# EIB_2xA79026-001_small_pins_v1_2_0_30mm.net
KiCad netlist of a schematic drawn in EAGLE
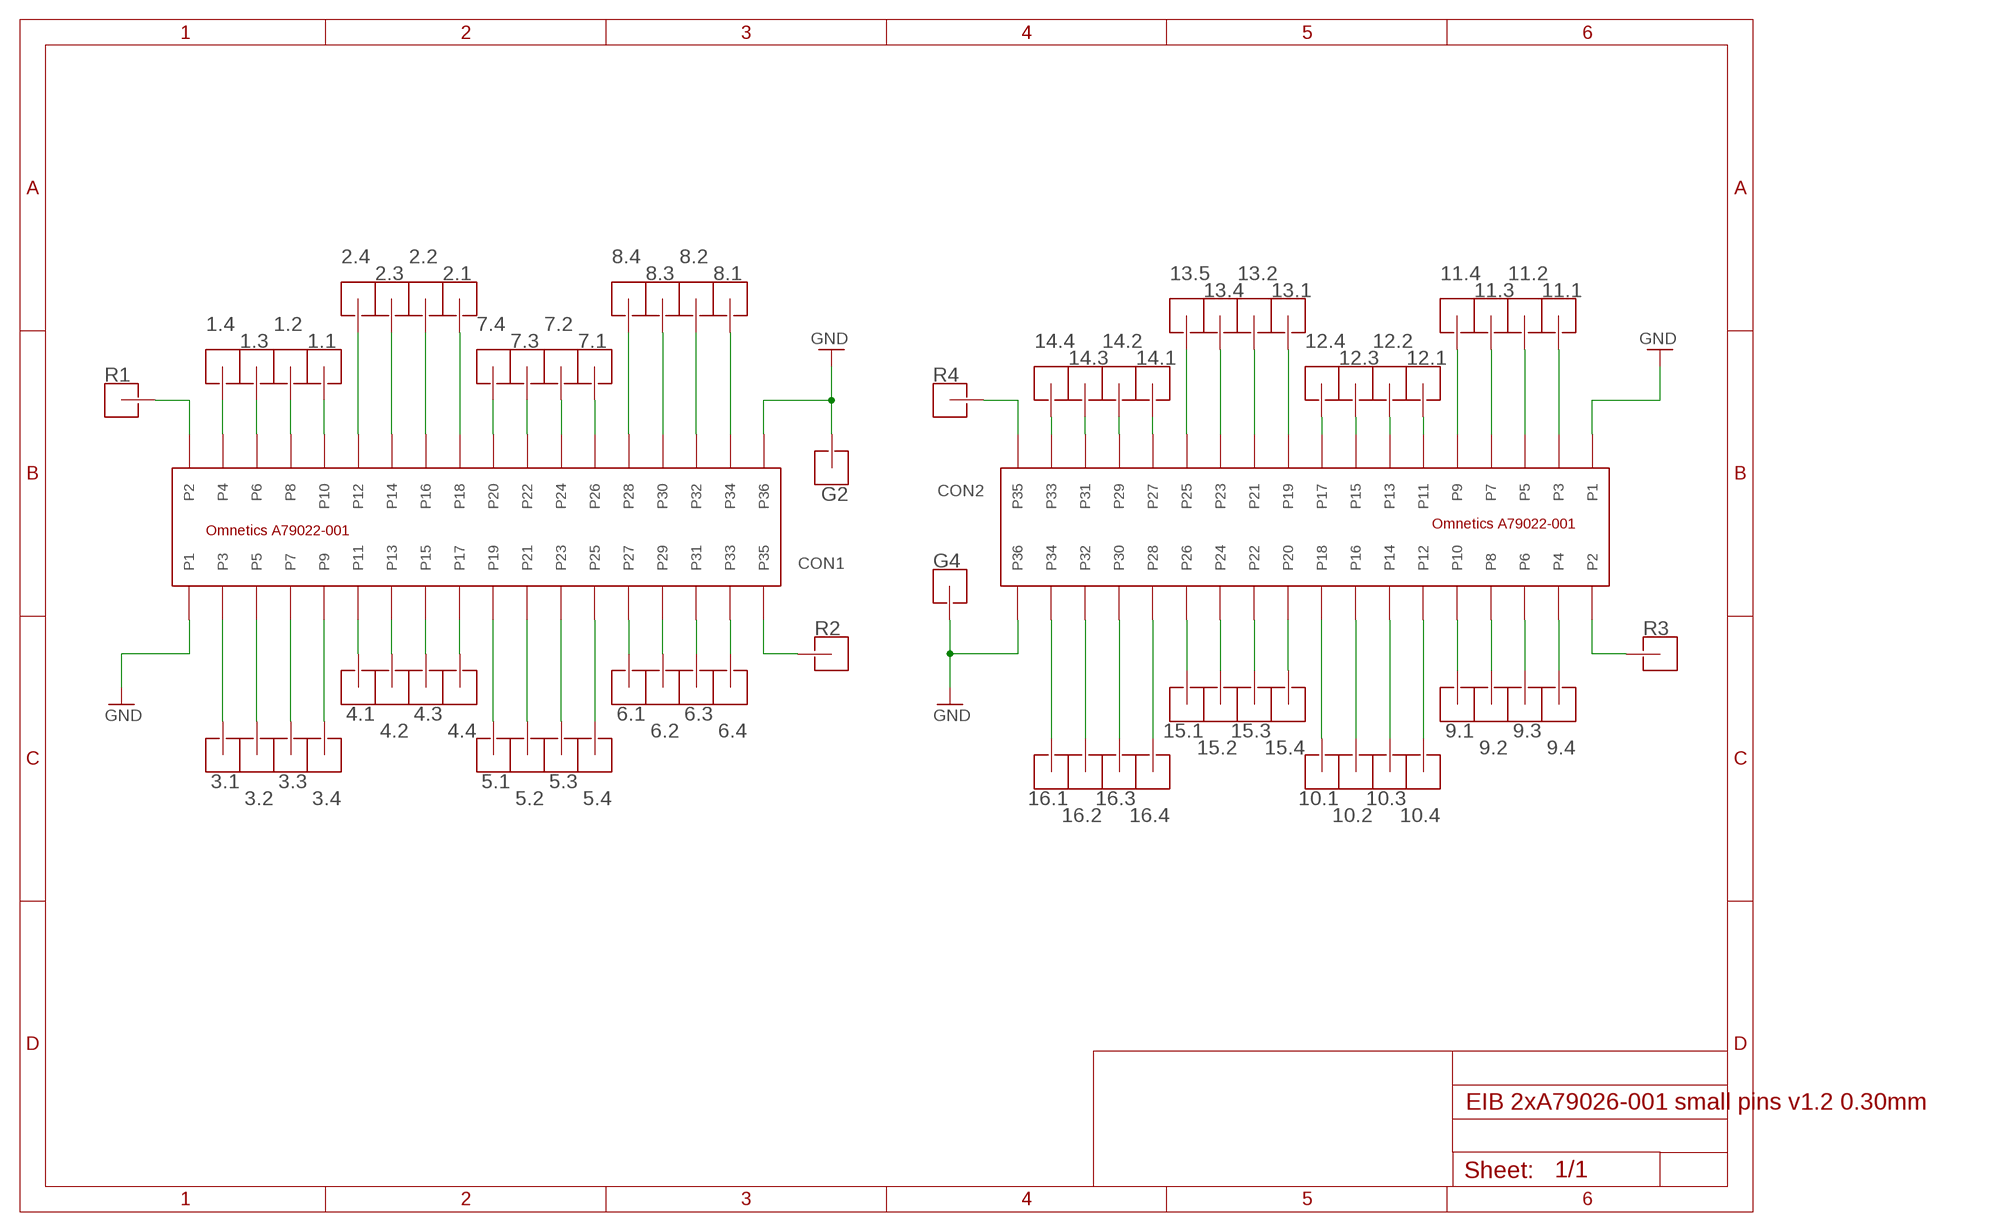
[diagram p0: schematic, sheet 1]

(export (version "E")
  (design (tool "Eeschema 10.0.6"))
  (components
    (comp (ref "1.1")
      (value "HOLE_S_G_PIN_V3")
      (footprint "eagle-import:SMALL_GOLD_PIN_V3")
      (libsource (lib "eagle-import") (part "HOLE_S_G_PIN_V3"))
    )
    (comp (ref "1.2")
      (value "HOLE_S_G_PIN_V3")
      (footprint "eagle-import:SMALL_GOLD_PIN_V3")
      (libsource (lib "eagle-import") (part "HOLE_S_G_PIN_V3"))
    )
    (comp (ref "1.3")
      (value "HOLE_S_G_PIN_V3")
      (footprint "eagle-import:SMALL_GOLD_PIN_V3")
      (libsource (lib "eagle-import") (part "HOLE_S_G_PIN_V3"))
    )
    (comp (ref "1.4")
      (value "HOLE_S_G_PIN_V3")
      (footprint "eagle-import:SMALL_GOLD_PIN_V3")
      (libsource (lib "eagle-import") (part "HOLE_S_G_PIN_V3"))
    )
    (comp (ref "2.1")
      (value "HOLE_S_G_PIN_V3")
      (footprint "eagle-import:SMALL_GOLD_PIN_V3")
      (libsource (lib "eagle-import") (part "HOLE_S_G_PIN_V3"))
    )
    (comp (ref "2.2")
      (value "HOLE_S_G_PIN_V3")
      (footprint "eagle-import:SMALL_GOLD_PIN_V3")
      (libsource (lib "eagle-import") (part "HOLE_S_G_PIN_V3"))
    )
    (comp (ref "2.3")
      (value "HOLE_S_G_PIN_V3")
      (footprint "eagle-import:SMALL_GOLD_PIN_V3")
      (libsource (lib "eagle-import") (part "HOLE_S_G_PIN_V3"))
    )
    (comp (ref "2.4")
      (value "HOLE_S_G_PIN_V3")
      (footprint "eagle-import:SMALL_GOLD_PIN_V3")
      (libsource (lib "eagle-import") (part "HOLE_S_G_PIN_V3"))
    )
    (comp (ref "3.1")
      (value "HOLE_S_G_PIN_V3")
      (footprint "eagle-import:SMALL_GOLD_PIN_V3")
      (libsource (lib "eagle-import") (part "HOLE_S_G_PIN_V3"))
    )
    (comp (ref "3.2")
      (value "HOLE_S_G_PIN_V3")
      (footprint "eagle-import:SMALL_GOLD_PIN_V3")
      (libsource (lib "eagle-import") (part "HOLE_S_G_PIN_V3"))
    )
    (comp (ref "3.3")
      (value "HOLE_S_G_PIN_V3")
      (footprint "eagle-import:SMALL_GOLD_PIN_V3")
      (libsource (lib "eagle-import") (part "HOLE_S_G_PIN_V3"))
    )
    (comp (ref "3.4")
      (value "HOLE_S_G_PIN_V3")
      (footprint "eagle-import:SMALL_GOLD_PIN_V3")
      (libsource (lib "eagle-import") (part "HOLE_S_G_PIN_V3"))
    )
    (comp (ref "4.1")
      (value "HOLE_S_G_PIN_V3")
      (footprint "eagle-import:SMALL_GOLD_PIN_V3")
      (libsource (lib "eagle-import") (part "HOLE_S_G_PIN_V3"))
    )
    (comp (ref "4.2")
      (value "HOLE_S_G_PIN_V3")
      (footprint "eagle-import:SMALL_GOLD_PIN_V3")
      (libsource (lib "eagle-import") (part "HOLE_S_G_PIN_V3"))
    )
    (comp (ref "4.3")
      (value "HOLE_S_G_PIN_V3")
      (footprint "eagle-import:SMALL_GOLD_PIN_V3")
      (libsource (lib "eagle-import") (part "HOLE_S_G_PIN_V3"))
    )
    (comp (ref "4.4")
      (value "HOLE_S_G_PIN_V3")
      (footprint "eagle-import:SMALL_GOLD_PIN_V3")
      (libsource (lib "eagle-import") (part "HOLE_S_G_PIN_V3"))
    )
    (comp (ref "5.1")
      (value "HOLE_S_G_PIN_V3")
      (footprint "eagle-import:SMALL_GOLD_PIN_V3")
      (libsource (lib "eagle-import") (part "HOLE_S_G_PIN_V3"))
    )
    (comp (ref "5.2")
      (value "HOLE_S_G_PIN_V3")
      (footprint "eagle-import:SMALL_GOLD_PIN_V3")
      (libsource (lib "eagle-import") (part "HOLE_S_G_PIN_V3"))
    )
    (comp (ref "5.3")
      (value "HOLE_S_G_PIN_V3")
      (footprint "eagle-import:SMALL_GOLD_PIN_V3")
      (libsource (lib "eagle-import") (part "HOLE_S_G_PIN_V3"))
    )
    (comp (ref "5.4")
      (value "HOLE_S_G_PIN_V3")
      (footprint "eagle-import:SMALL_GOLD_PIN_V3")
      (libsource (lib "eagle-import") (part "HOLE_S_G_PIN_V3"))
    )
    (comp (ref "6.1")
      (value "HOLE_S_G_PIN_V3")
      (footprint "eagle-import:SMALL_GOLD_PIN_V3")
      (libsource (lib "eagle-import") (part "HOLE_S_G_PIN_V3"))
    )
    (comp (ref "6.2")
      (value "HOLE_S_G_PIN_V3")
      (footprint "eagle-import:SMALL_GOLD_PIN_V3")
      (libsource (lib "eagle-import") (part "HOLE_S_G_PIN_V3"))
    )
    (comp (ref "6.3")
      (value "HOLE_S_G_PIN_V3")
      (footprint "eagle-import:SMALL_GOLD_PIN_V3")
      (libsource (lib "eagle-import") (part "HOLE_S_G_PIN_V3"))
    )
    (comp (ref "6.4")
      (value "HOLE_S_G_PIN_V3")
      (footprint "eagle-import:SMALL_GOLD_PIN_V3")
      (libsource (lib "eagle-import") (part "HOLE_S_G_PIN_V3"))
    )
    (comp (ref "7.1")
      (value "HOLE_S_G_PIN_V3")
      (footprint "eagle-import:SMALL_GOLD_PIN_V3")
      (libsource (lib "eagle-import") (part "HOLE_S_G_PIN_V3"))
    )
    (comp (ref "7.2")
      (value "HOLE_S_G_PIN_V3")
      (footprint "eagle-import:SMALL_GOLD_PIN_V3")
      (libsource (lib "eagle-import") (part "HOLE_S_G_PIN_V3"))
    )
    (comp (ref "7.3")
      (value "HOLE_S_G_PIN_V3")
      (footprint "eagle-import:SMALL_GOLD_PIN_V3")
      (libsource (lib "eagle-import") (part "HOLE_S_G_PIN_V3"))
    )
    (comp (ref "7.4")
      (value "HOLE_S_G_PIN_V3")
      (footprint "eagle-import:SMALL_GOLD_PIN_V3")
      (libsource (lib "eagle-import") (part "HOLE_S_G_PIN_V3"))
    )
    (comp (ref "8.1")
      (value "HOLE_S_G_PIN_V3")
      (footprint "eagle-import:SMALL_GOLD_PIN_V3")
      (libsource (lib "eagle-import") (part "HOLE_S_G_PIN_V3"))
    )
    (comp (ref "8.2")
      (value "HOLE_S_G_PIN_V3")
      (footprint "eagle-import:SMALL_GOLD_PIN_V3")
      (libsource (lib "eagle-import") (part "HOLE_S_G_PIN_V3"))
    )
    (comp (ref "8.3")
      (value "HOLE_S_G_PIN_V3")
      (footprint "eagle-import:SMALL_GOLD_PIN_V3")
      (libsource (lib "eagle-import") (part "HOLE_S_G_PIN_V3"))
    )
    (comp (ref "8.4")
      (value "HOLE_S_G_PIN_V3")
      (footprint "eagle-import:SMALL_GOLD_PIN_V3")
      (libsource (lib "eagle-import") (part "HOLE_S_G_PIN_V3"))
    )
    (comp (ref "9.1")
      (value "HOLE_S_G_PIN_V3")
      (footprint "eagle-import:SMALL_GOLD_PIN_V3")
      (libsource (lib "eagle-import") (part "HOLE_S_G_PIN_V3"))
    )
    (comp (ref "9.2")
      (value "HOLE_S_G_PIN_V3")
      (footprint "eagle-import:SMALL_GOLD_PIN_V3")
      (libsource (lib "eagle-import") (part "HOLE_S_G_PIN_V3"))
    )
    (comp (ref "9.3")
      (value "HOLE_S_G_PIN_V3")
      (footprint "eagle-import:SMALL_GOLD_PIN_V3")
      (libsource (lib "eagle-import") (part "HOLE_S_G_PIN_V3"))
    )
    (comp (ref "9.4")
      (value "HOLE_S_G_PIN_V3")
      (footprint "eagle-import:SMALL_GOLD_PIN_V3")
      (libsource (lib "eagle-import") (part "HOLE_S_G_PIN_V3"))
    )
    (comp (ref "10.1")
      (value "HOLE_S_G_PIN_V3")
      (footprint "eagle-import:SMALL_GOLD_PIN_V3")
      (libsource (lib "eagle-import") (part "HOLE_S_G_PIN_V3"))
    )
    (comp (ref "10.2")
      (value "HOLE_S_G_PIN_V3")
      (footprint "eagle-import:SMALL_GOLD_PIN_V3")
      (libsource (lib "eagle-import") (part "HOLE_S_G_PIN_V3"))
    )
    (comp (ref "10.3")
      (value "HOLE_S_G_PIN_V3")
      (footprint "eagle-import:SMALL_GOLD_PIN_V3")
      (libsource (lib "eagle-import") (part "HOLE_S_G_PIN_V3"))
    )
    (comp (ref "10.4")
      (value "HOLE_S_G_PIN_V3")
      (footprint "eagle-import:SMALL_GOLD_PIN_V3")
      (libsource (lib "eagle-import") (part "HOLE_S_G_PIN_V3"))
    )
    (comp (ref "11.1")
      (value "HOLE_S_G_PIN_V3")
      (footprint "eagle-import:SMALL_GOLD_PIN_V3")
      (libsource (lib "eagle-import") (part "HOLE_S_G_PIN_V3"))
    )
    (comp (ref "11.2")
      (value "HOLE_S_G_PIN_V3")
      (footprint "eagle-import:SMALL_GOLD_PIN_V3")
      (libsource (lib "eagle-import") (part "HOLE_S_G_PIN_V3"))
    )
    (comp (ref "11.3")
      (value "HOLE_S_G_PIN_V3")
      (footprint "eagle-import:SMALL_GOLD_PIN_V3")
      (libsource (lib "eagle-import") (part "HOLE_S_G_PIN_V3"))
    )
    (comp (ref "11.4")
      (value "HOLE_S_G_PIN_V3")
      (footprint "eagle-import:SMALL_GOLD_PIN_V3")
      (libsource (lib "eagle-import") (part "HOLE_S_G_PIN_V3"))
    )
    (comp (ref "12.1")
      (value "HOLE_S_G_PIN_V3")
      (footprint "eagle-import:SMALL_GOLD_PIN_V3")
      (libsource (lib "eagle-import") (part "HOLE_S_G_PIN_V3"))
    )
    (comp (ref "12.2")
      (value "HOLE_S_G_PIN_V3")
      (footprint "eagle-import:SMALL_GOLD_PIN_V3")
      (libsource (lib "eagle-import") (part "HOLE_S_G_PIN_V3"))
    )
    (comp (ref "12.3")
      (value "HOLE_S_G_PIN_V3")
      (footprint "eagle-import:SMALL_GOLD_PIN_V3")
      (libsource (lib "eagle-import") (part "HOLE_S_G_PIN_V3"))
    )
    (comp (ref "12.4")
      (value "HOLE_S_G_PIN_V3")
      (footprint "eagle-import:SMALL_GOLD_PIN_V3")
      (libsource (lib "eagle-import") (part "HOLE_S_G_PIN_V3"))
    )
    (comp (ref "13.1")
      (value "HOLE_S_G_PIN_V3")
      (footprint "eagle-import:SMALL_GOLD_PIN_V3")
      (libsource (lib "eagle-import") (part "HOLE_S_G_PIN_V3"))
    )
    (comp (ref "13.2")
      (value "HOLE_S_G_PIN_V3")
      (footprint "eagle-import:SMALL_GOLD_PIN_V3")
      (libsource (lib "eagle-import") (part "HOLE_S_G_PIN_V3"))
    )
    (comp (ref "13.4")
      (value "HOLE_S_G_PIN_V3")
      (footprint "eagle-import:SMALL_GOLD_PIN_V3")
      (libsource (lib "eagle-import") (part "HOLE_S_G_PIN_V3"))
    )
    (comp (ref "13.5")
      (value "HOLE_S_G_PIN_V3")
      (footprint "eagle-import:SMALL_GOLD_PIN_V3")
      (libsource (lib "eagle-import") (part "HOLE_S_G_PIN_V3"))
    )
    (comp (ref "14.1")
      (value "HOLE_S_G_PIN_V3")
      (footprint "eagle-import:SMALL_GOLD_PIN_V3")
      (libsource (lib "eagle-import") (part "HOLE_S_G_PIN_V3"))
    )
    (comp (ref "14.2")
      (value "HOLE_S_G_PIN_V3")
      (footprint "eagle-import:SMALL_GOLD_PIN_V3")
      (libsource (lib "eagle-import") (part "HOLE_S_G_PIN_V3"))
    )
    (comp (ref "14.3")
      (value "HOLE_S_G_PIN_V3")
      (footprint "eagle-import:SMALL_GOLD_PIN_V3")
      (libsource (lib "eagle-import") (part "HOLE_S_G_PIN_V3"))
    )
    (comp (ref "14.4")
      (value "HOLE_S_G_PIN_V3")
      (footprint "eagle-import:SMALL_GOLD_PIN_V3")
      (libsource (lib "eagle-import") (part "HOLE_S_G_PIN_V3"))
    )
    (comp (ref "15.1")
      (value "HOLE_S_G_PIN_V3")
      (footprint "eagle-import:SMALL_GOLD_PIN_V3")
      (libsource (lib "eagle-import") (part "HOLE_S_G_PIN_V3"))
    )
    (comp (ref "15.2")
      (value "HOLE_S_G_PIN_V3")
      (footprint "eagle-import:SMALL_GOLD_PIN_V3")
      (libsource (lib "eagle-import") (part "HOLE_S_G_PIN_V3"))
    )
    (comp (ref "15.3")
      (value "HOLE_S_G_PIN_V3")
      (footprint "eagle-import:SMALL_GOLD_PIN_V3")
      (libsource (lib "eagle-import") (part "HOLE_S_G_PIN_V3"))
    )
    (comp (ref "15.4")
      (value "HOLE_S_G_PIN_V3")
      (footprint "eagle-import:SMALL_GOLD_PIN_V3")
      (libsource (lib "eagle-import") (part "HOLE_S_G_PIN_V3"))
    )
    (comp (ref "16.1")
      (value "HOLE_S_G_PIN_V3")
      (footprint "eagle-import:SMALL_GOLD_PIN_V3")
      (libsource (lib "eagle-import") (part "HOLE_S_G_PIN_V3"))
    )
    (comp (ref "16.2")
      (value "HOLE_S_G_PIN_V3")
      (footprint "eagle-import:SMALL_GOLD_PIN_V3")
      (libsource (lib "eagle-import") (part "HOLE_S_G_PIN_V3"))
    )
    (comp (ref "16.3")
      (value "HOLE_S_G_PIN_V3")
      (footprint "eagle-import:SMALL_GOLD_PIN_V3")
      (libsource (lib "eagle-import") (part "HOLE_S_G_PIN_V3"))
    )
    (comp (ref "16.4")
      (value "HOLE_S_G_PIN_V3")
      (footprint "eagle-import:SMALL_GOLD_PIN_V3")
      (libsource (lib "eagle-import") (part "HOLE_S_G_PIN_V3"))
    )
    (comp (ref "CON1")
      (value "A79022-001_MALESMD")
      (footprint "eagle-import:A79026-001_MALE")
      (libsource (lib "eagle-import") (part "A79022-001_MALESMD"))
    )
    (comp (ref "CON2")
      (value "A79022-001_MALESMD")
      (footprint "eagle-import:A79026-001_MALE")
      (libsource (lib "eagle-import") (part "A79022-001_MALESMD"))
    )
    (comp (ref "G2")
      (value "HOLE_S_G_PIN_V3")
      (footprint "eagle-import:SMALL_GOLD_PIN_V3")
      (libsource (lib "eagle-import") (part "HOLE_S_G_PIN_V3"))
    )
    (comp (ref "G4")
      (value "HOLE_S_G_PIN_V3")
      (footprint "eagle-import:SMALL_GOLD_PIN_V3")
      (libsource (lib "eagle-import") (part "HOLE_S_G_PIN_V3"))
    )
    (comp (ref "R1")
      (value "HOLE_S_G_PIN_V3")
      (footprint "eagle-import:SMALL_GOLD_PIN_V3")
      (libsource (lib "eagle-import") (part "HOLE_S_G_PIN_V3"))
    )
    (comp (ref "R2")
      (value "HOLE_S_G_PIN_V3")
      (footprint "eagle-import:SMALL_GOLD_PIN_V3")
      (libsource (lib "eagle-import") (part "HOLE_S_G_PIN_V3"))
    )
    (comp (ref "R3")
      (value "HOLE_S_G_PIN_V3")
      (footprint "eagle-import:SMALL_GOLD_PIN_V3")
      (libsource (lib "eagle-import") (part "HOLE_S_G_PIN_V3"))
    )
    (comp (ref "R4")
      (value "HOLE_S_G_PIN_V3")
      (footprint "eagle-import:SMALL_GOLD_PIN_V3")
      (libsource (lib "eagle-import") (part "HOLE_S_G_PIN_V3"))
    )
  )
  (nets
    (net (code "1") (name "GND") (class "Default")
      (node (ref "CON1") (pin "P1") (pinfunction "P1_P1") (pintype "bidirectional"))
      (node (ref "CON1") (pin "P36") (pinfunction "P36_P36") (pintype "bidirectional"))
      (node (ref "CON2") (pin "P1") (pinfunction "P1_P1") (pintype "bidirectional"))
      (node (ref "CON2") (pin "P36") (pinfunction "P36_P36") (pintype "bidirectional"))
      (node (ref "G2") (pin "P$1") (pinfunction "P$1_P$1") (pintype "bidirectional"))
      (node (ref "G4") (pin "P$1") (pinfunction "P$1_P$1") (pintype "bidirectional"))
    )
    (net (code "2") (name "Net-(1.1-PadP$1)") (class "Default")
      (node (ref "1.1") (pin "P$1") (pinfunction "P$1_P$1") (pintype "bidirectional"))
      (node (ref "CON1") (pin "P10") (pinfunction "P10_P10") (pintype "bidirectional"))
    )
    (net (code "3") (name "Net-(1.2-PadP$1)") (class "Default")
      (node (ref "1.2") (pin "P$1") (pinfunction "P$1_P$1") (pintype "bidirectional"))
      (node (ref "CON1") (pin "P8") (pinfunction "P8_P8") (pintype "bidirectional"))
    )
    (net (code "4") (name "Net-(1.3-PadP$1)") (class "Default")
      (node (ref "1.3") (pin "P$1") (pinfunction "P$1_P$1") (pintype "bidirectional"))
      (node (ref "CON1") (pin "P6") (pinfunction "P6_P6") (pintype "bidirectional"))
    )
    (net (code "5") (name "Net-(1.4-PadP$1)") (class "Default")
      (node (ref "1.4") (pin "P$1") (pinfunction "P$1_P$1") (pintype "bidirectional"))
      (node (ref "CON1") (pin "P4") (pinfunction "P4_P4") (pintype "bidirectional"))
    )
    (net (code "6") (name "Net-(2.1-PadP$1)") (class "Default")
      (node (ref "2.1") (pin "P$1") (pinfunction "P$1_P$1") (pintype "bidirectional"))
      (node (ref "CON1") (pin "P18") (pinfunction "P18_P18") (pintype "bidirectional"))
    )
    (net (code "7") (name "Net-(2.2-PadP$1)") (class "Default")
      (node (ref "2.2") (pin "P$1") (pinfunction "P$1_P$1") (pintype "bidirectional"))
      (node (ref "CON1") (pin "P16") (pinfunction "P16_P16") (pintype "bidirectional"))
    )
    (net (code "8") (name "Net-(2.3-PadP$1)") (class "Default")
      (node (ref "2.3") (pin "P$1") (pinfunction "P$1_P$1") (pintype "bidirectional"))
      (node (ref "CON1") (pin "P14") (pinfunction "P14_P14") (pintype "bidirectional"))
    )
    (net (code "9") (name "Net-(2.4-PadP$1)") (class "Default")
      (node (ref "2.4") (pin "P$1") (pinfunction "P$1_P$1") (pintype "bidirectional"))
      (node (ref "CON1") (pin "P12") (pinfunction "P12_P12") (pintype "bidirectional"))
    )
    (net (code "10") (name "Net-(3.1-PadP$1)") (class "Default")
      (node (ref "3.1") (pin "P$1") (pinfunction "P$1_P$1") (pintype "bidirectional"))
      (node (ref "CON1") (pin "P3") (pinfunction "P3_P3") (pintype "bidirectional"))
    )
    (net (code "11") (name "Net-(3.2-PadP$1)") (class "Default")
      (node (ref "3.2") (pin "P$1") (pinfunction "P$1_P$1") (pintype "bidirectional"))
      (node (ref "CON1") (pin "P5") (pinfunction "P5_P5") (pintype "bidirectional"))
    )
    (net (code "12") (name "Net-(3.3-PadP$1)") (class "Default")
      (node (ref "3.3") (pin "P$1") (pinfunction "P$1_P$1") (pintype "bidirectional"))
      (node (ref "CON1") (pin "P7") (pinfunction "P7_P7") (pintype "bidirectional"))
    )
    (net (code "13") (name "Net-(3.4-PadP$1)") (class "Default")
      (node (ref "3.4") (pin "P$1") (pinfunction "P$1_P$1") (pintype "bidirectional"))
      (node (ref "CON1") (pin "P9") (pinfunction "P9_P9") (pintype "bidirectional"))
    )
    (net (code "14") (name "Net-(4.1-PadP$1)") (class "Default")
      (node (ref "4.1") (pin "P$1") (pinfunction "P$1_P$1") (pintype "bidirectional"))
      (node (ref "CON1") (pin "P11") (pinfunction "P11_P11") (pintype "bidirectional"))
    )
    (net (code "15") (name "Net-(4.2-PadP$1)") (class "Default")
      (node (ref "4.2") (pin "P$1") (pinfunction "P$1_P$1") (pintype "bidirectional"))
      (node (ref "CON1") (pin "P13") (pinfunction "P13_P13") (pintype "bidirectional"))
    )
    (net (code "16") (name "Net-(4.3-PadP$1)") (class "Default")
      (node (ref "4.3") (pin "P$1") (pinfunction "P$1_P$1") (pintype "bidirectional"))
      (node (ref "CON1") (pin "P15") (pinfunction "P15_P15") (pintype "bidirectional"))
    )
    (net (code "17") (name "Net-(4.4-PadP$1)") (class "Default")
      (node (ref "4.4") (pin "P$1") (pinfunction "P$1_P$1") (pintype "bidirectional"))
      (node (ref "CON1") (pin "P17") (pinfunction "P17_P17") (pintype "bidirectional"))
    )
    (net (code "18") (name "Net-(5.1-PadP$1)") (class "Default")
      (node (ref "5.1") (pin "P$1") (pinfunction "P$1_P$1") (pintype "bidirectional"))
      (node (ref "CON1") (pin "P19") (pinfunction "P19_P19") (pintype "bidirectional"))
    )
    (net (code "19") (name "Net-(5.2-PadP$1)") (class "Default")
      (node (ref "5.2") (pin "P$1") (pinfunction "P$1_P$1") (pintype "bidirectional"))
      (node (ref "CON1") (pin "P21") (pinfunction "P21_P21") (pintype "bidirectional"))
    )
    (net (code "20") (name "Net-(5.3-PadP$1)") (class "Default")
      (node (ref "5.3") (pin "P$1") (pinfunction "P$1_P$1") (pintype "bidirectional"))
      (node (ref "CON1") (pin "P23") (pinfunction "P23_P23") (pintype "bidirectional"))
    )
    (net (code "21") (name "Net-(5.4-PadP$1)") (class "Default")
      (node (ref "5.4") (pin "P$1") (pinfunction "P$1_P$1") (pintype "bidirectional"))
      (node (ref "CON1") (pin "P25") (pinfunction "P25_P25") (pintype "bidirectional"))
    )
    (net (code "22") (name "Net-(6.1-PadP$1)") (class "Default")
      (node (ref "6.1") (pin "P$1") (pinfunction "P$1_P$1") (pintype "bidirectional"))
      (node (ref "CON1") (pin "P27") (pinfunction "P27_P27") (pintype "bidirectional"))
    )
    (net (code "23") (name "Net-(6.2-PadP$1)") (class "Default")
      (node (ref "6.2") (pin "P$1") (pinfunction "P$1_P$1") (pintype "bidirectional"))
      (node (ref "CON1") (pin "P29") (pinfunction "P29_P29") (pintype "bidirectional"))
    )
    (net (code "24") (name "Net-(6.3-PadP$1)") (class "Default")
      (node (ref "6.3") (pin "P$1") (pinfunction "P$1_P$1") (pintype "bidirectional"))
      (node (ref "CON1") (pin "P31") (pinfunction "P31_P31") (pintype "bidirectional"))
    )
    (net (code "25") (name "Net-(6.4-PadP$1)") (class "Default")
      (node (ref "6.4") (pin "P$1") (pinfunction "P$1_P$1") (pintype "bidirectional"))
      (node (ref "CON1") (pin "P33") (pinfunction "P33_P33") (pintype "bidirectional"))
    )
    (net (code "26") (name "Net-(7.1-PadP$1)") (class "Default")
      (node (ref "7.1") (pin "P$1") (pinfunction "P$1_P$1") (pintype "bidirectional"))
      (node (ref "CON1") (pin "P26") (pinfunction "P26_P26") (pintype "bidirectional"))
    )
    (net (code "27") (name "Net-(7.2-PadP$1)") (class "Default")
      (node (ref "7.2") (pin "P$1") (pinfunction "P$1_P$1") (pintype "bidirectional"))
      (node (ref "CON1") (pin "P24") (pinfunction "P24_P24") (pintype "bidirectional"))
    )
    (net (code "28") (name "Net-(7.3-PadP$1)") (class "Default")
      (node (ref "7.3") (pin "P$1") (pinfunction "P$1_P$1") (pintype "bidirectional"))
      (node (ref "CON1") (pin "P22") (pinfunction "P22_P22") (pintype "bidirectional"))
    )
    (net (code "29") (name "Net-(7.4-PadP$1)") (class "Default")
      (node (ref "7.4") (pin "P$1") (pinfunction "P$1_P$1") (pintype "bidirectional"))
      (node (ref "CON1") (pin "P20") (pinfunction "P20_P20") (pintype "bidirectional"))
    )
    (net (code "30") (name "Net-(8.1-PadP$1)") (class "Default")
      (node (ref "8.1") (pin "P$1") (pinfunction "P$1_P$1") (pintype "bidirectional"))
      (node (ref "CON1") (pin "P34") (pinfunction "P34_P34") (pintype "bidirectional"))
    )
    (net (code "31") (name "Net-(8.2-PadP$1)") (class "Default")
      (node (ref "8.2") (pin "P$1") (pinfunction "P$1_P$1") (pintype "bidirectional"))
      (node (ref "CON1") (pin "P32") (pinfunction "P32_P32") (pintype "bidirectional"))
    )
    (net (code "32") (name "Net-(8.3-PadP$1)") (class "Default")
      (node (ref "8.3") (pin "P$1") (pinfunction "P$1_P$1") (pintype "bidirectional"))
      (node (ref "CON1") (pin "P30") (pinfunction "P30_P30") (pintype "bidirectional"))
    )
    (net (code "33") (name "Net-(8.4-PadP$1)") (class "Default")
      (node (ref "8.4") (pin "P$1") (pinfunction "P$1_P$1") (pintype "bidirectional"))
      (node (ref "CON1") (pin "P28") (pinfunction "P28_P28") (pintype "bidirectional"))
    )
    (net (code "34") (name "Net-(9.1-PadP$1)") (class "Default")
      (node (ref "9.1") (pin "P$1") (pinfunction "P$1_P$1") (pintype "bidirectional"))
      (node (ref "CON2") (pin "P10") (pinfunction "P10_P10") (pintype "bidirectional"))
    )
    (net (code "35") (name "Net-(9.2-PadP$1)") (class "Default")
      (node (ref "9.2") (pin "P$1") (pinfunction "P$1_P$1") (pintype "bidirectional"))
      (node (ref "CON2") (pin "P8") (pinfunction "P8_P8") (pintype "bidirectional"))
    )
    (net (code "36") (name "Net-(9.3-PadP$1)") (class "Default")
      (node (ref "9.3") (pin "P$1") (pinfunction "P$1_P$1") (pintype "bidirectional"))
      (node (ref "CON2") (pin "P6") (pinfunction "P6_P6") (pintype "bidirectional"))
    )
    (net (code "37") (name "Net-(9.4-PadP$1)") (class "Default")
      (node (ref "9.4") (pin "P$1") (pinfunction "P$1_P$1") (pintype "bidirectional"))
      (node (ref "CON2") (pin "P4") (pinfunction "P4_P4") (pintype "bidirectional"))
    )
    (net (code "38") (name "Net-(10.1-PadP$1)") (class "Default")
      (node (ref "10.1") (pin "P$1") (pinfunction "P$1_P$1") (pintype "bidirectional"))
      (node (ref "CON2") (pin "P18") (pinfunction "P18_P18") (pintype "bidirectional"))
    )
    (net (code "39") (name "Net-(10.2-PadP$1)") (class "Default")
      (node (ref "10.2") (pin "P$1") (pinfunction "P$1_P$1") (pintype "bidirectional"))
      (node (ref "CON2") (pin "P16") (pinfunction "P16_P16") (pintype "bidirectional"))
    )
    (net (code "40") (name "Net-(10.3-PadP$1)") (class "Default")
      (node (ref "10.3") (pin "P$1") (pinfunction "P$1_P$1") (pintype "bidirectional"))
      (node (ref "CON2") (pin "P14") (pinfunction "P14_P14") (pintype "bidirectional"))
    )
    (net (code "41") (name "Net-(10.4-PadP$1)") (class "Default")
      (node (ref "10.4") (pin "P$1") (pinfunction "P$1_P$1") (pintype "bidirectional"))
      (node (ref "CON2") (pin "P12") (pinfunction "P12_P12") (pintype "bidirectional"))
    )
    (net (code "42") (name "Net-(11.1-PadP$1)") (class "Default")
      (node (ref "11.1") (pin "P$1") (pinfunction "P$1_P$1") (pintype "bidirectional"))
      (node (ref "CON2") (pin "P3") (pinfunction "P3_P3") (pintype "bidirectional"))
    )
    (net (code "43") (name "Net-(11.2-PadP$1)") (class "Default")
      (node (ref "11.2") (pin "P$1") (pinfunction "P$1_P$1") (pintype "bidirectional"))
      (node (ref "CON2") (pin "P5") (pinfunction "P5_P5") (pintype "bidirectional"))
    )
    (net (code "44") (name "Net-(11.3-PadP$1)") (class "Default")
      (node (ref "11.3") (pin "P$1") (pinfunction "P$1_P$1") (pintype "bidirectional"))
      (node (ref "CON2") (pin "P7") (pinfunction "P7_P7") (pintype "bidirectional"))
    )
    (net (code "45") (name "Net-(11.4-PadP$1)") (class "Default")
      (node (ref "11.4") (pin "P$1") (pinfunction "P$1_P$1") (pintype "bidirectional"))
      (node (ref "CON2") (pin "P9") (pinfunction "P9_P9") (pintype "bidirectional"))
    )
    (net (code "46") (name "Net-(12.1-PadP$1)") (class "Default")
      (node (ref "12.1") (pin "P$1") (pinfunction "P$1_P$1") (pintype "bidirectional"))
      (node (ref "CON2") (pin "P11") (pinfunction "P11_P11") (pintype "bidirectional"))
    )
    (net (code "47") (name "Net-(12.2-PadP$1)") (class "Default")
      (node (ref "12.2") (pin "P$1") (pinfunction "P$1_P$1") (pintype "bidirectional"))
      (node (ref "CON2") (pin "P13") (pinfunction "P13_P13") (pintype "bidirectional"))
    )
    (net (code "48") (name "Net-(12.3-PadP$1)") (class "Default")
      (node (ref "12.3") (pin "P$1") (pinfunction "P$1_P$1") (pintype "bidirectional"))
      (node (ref "CON2") (pin "P15") (pinfunction "P15_P15") (pintype "bidirectional"))
    )
    (net (code "49") (name "Net-(12.4-PadP$1)") (class "Default")
      (node (ref "12.4") (pin "P$1") (pinfunction "P$1_P$1") (pintype "bidirectional"))
      (node (ref "CON2") (pin "P17") (pinfunction "P17_P17") (pintype "bidirectional"))
    )
    (net (code "50") (name "Net-(13.1-PadP$1)") (class "Default")
      (node (ref "13.1") (pin "P$1") (pinfunction "P$1_P$1") (pintype "bidirectional"))
      (node (ref "CON2") (pin "P19") (pinfunction "P19_P19") (pintype "bidirectional"))
    )
    (net (code "51") (name "Net-(13.2-PadP$1)") (class "Default")
      (node (ref "13.2") (pin "P$1") (pinfunction "P$1_P$1") (pintype "bidirectional"))
      (node (ref "CON2") (pin "P21") (pinfunction "P21_P21") (pintype "bidirectional"))
    )
    (net (code "52") (name "Net-(13.4-PadP$1)") (class "Default")
      (node (ref "13.4") (pin "P$1") (pinfunction "P$1_P$1") (pintype "bidirectional"))
      (node (ref "CON2") (pin "P23") (pinfunction "P23_P23") (pintype "bidirectional"))
    )
    (net (code "53") (name "Net-(13.5-PadP$1)") (class "Default")
      (node (ref "13.5") (pin "P$1") (pinfunction "P$1_P$1") (pintype "bidirectional"))
      (node (ref "CON2") (pin "P25") (pinfunction "P25_P25") (pintype "bidirectional"))
    )
    (net (code "54") (name "Net-(14.1-PadP$1)") (class "Default")
      (node (ref "14.1") (pin "P$1") (pinfunction "P$1_P$1") (pintype "bidirectional"))
      (node (ref "CON2") (pin "P27") (pinfunction "P27_P27") (pintype "bidirectional"))
    )
    (net (code "55") (name "Net-(14.2-PadP$1)") (class "Default")
      (node (ref "14.2") (pin "P$1") (pinfunction "P$1_P$1") (pintype "bidirectional"))
      (node (ref "CON2") (pin "P29") (pinfunction "P29_P29") (pintype "bidirectional"))
    )
    (net (code "56") (name "Net-(14.3-PadP$1)") (class "Default")
      (node (ref "14.3") (pin "P$1") (pinfunction "P$1_P$1") (pintype "bidirectional"))
      (node (ref "CON2") (pin "P31") (pinfunction "P31_P31") (pintype "bidirectional"))
    )
    (net (code "57") (name "Net-(14.4-PadP$1)") (class "Default")
      (node (ref "14.4") (pin "P$1") (pinfunction "P$1_P$1") (pintype "bidirectional"))
      (node (ref "CON2") (pin "P33") (pinfunction "P33_P33") (pintype "bidirectional"))
    )
    (net (code "58") (name "Net-(15.1-PadP$1)") (class "Default")
      (node (ref "15.1") (pin "P$1") (pinfunction "P$1_P$1") (pintype "bidirectional"))
      (node (ref "CON2") (pin "P26") (pinfunction "P26_P26") (pintype "bidirectional"))
    )
    (net (code "59") (name "Net-(15.2-PadP$1)") (class "Default")
      (node (ref "15.2") (pin "P$1") (pinfunction "P$1_P$1") (pintype "bidirectional"))
      (node (ref "CON2") (pin "P24") (pinfunction "P24_P24") (pintype "bidirectional"))
    )
    (net (code "60") (name "Net-(15.3-PadP$1)") (class "Default")
      (node (ref "15.3") (pin "P$1") (pinfunction "P$1_P$1") (pintype "bidirectional"))
      (node (ref "CON2") (pin "P22") (pinfunction "P22_P22") (pintype "bidirectional"))
    )
    (net (code "61") (name "Net-(15.4-PadP$1)") (class "Default")
      (node (ref "15.4") (pin "P$1") (pinfunction "P$1_P$1") (pintype "bidirectional"))
      (node (ref "CON2") (pin "P20") (pinfunction "P20_P20") (pintype "bidirectional"))
    )
    (net (code "62") (name "Net-(16.1-PadP$1)") (class "Default")
      (node (ref "16.1") (pin "P$1") (pinfunction "P$1_P$1") (pintype "bidirectional"))
      (node (ref "CON2") (pin "P34") (pinfunction "P34_P34") (pintype "bidirectional"))
    )
    (net (code "63") (name "Net-(16.2-PadP$1)") (class "Default")
      (node (ref "16.2") (pin "P$1") (pinfunction "P$1_P$1") (pintype "bidirectional"))
      (node (ref "CON2") (pin "P32") (pinfunction "P32_P32") (pintype "bidirectional"))
    )
    (net (code "64") (name "Net-(16.3-PadP$1)") (class "Default")
      (node (ref "16.3") (pin "P$1") (pinfunction "P$1_P$1") (pintype "bidirectional"))
      (node (ref "CON2") (pin "P30") (pinfunction "P30_P30") (pintype "bidirectional"))
    )
    (net (code "65") (name "Net-(16.4-PadP$1)") (class "Default")
      (node (ref "16.4") (pin "P$1") (pinfunction "P$1_P$1") (pintype "bidirectional"))
      (node (ref "CON2") (pin "P28") (pinfunction "P28_P28") (pintype "bidirectional"))
    )
    (net (code "66") (name "Net-(CON1-PadP2)") (class "Default")
      (node (ref "CON1") (pin "P2") (pinfunction "P2_P2") (pintype "bidirectional"))
      (node (ref "R1") (pin "P$1") (pinfunction "P$1_P$1") (pintype "bidirectional"))
    )
    (net (code "67") (name "Net-(CON1-PadP35)") (class "Default")
      (node (ref "CON1") (pin "P35") (pinfunction "P35_P35") (pintype "bidirectional"))
      (node (ref "R2") (pin "P$1") (pinfunction "P$1_P$1") (pintype "bidirectional"))
    )
    (net (code "68") (name "Net-(CON2-PadP2)") (class "Default")
      (node (ref "CON2") (pin "P2") (pinfunction "P2_P2") (pintype "bidirectional"))
      (node (ref "R3") (pin "P$1") (pinfunction "P$1_P$1") (pintype "bidirectional"))
    )
    (net (code "69") (name "Net-(CON2-PadP35)") (class "Default")
      (node (ref "CON2") (pin "P35") (pinfunction "P35_P35") (pintype "bidirectional"))
      (node (ref "R4") (pin "P$1") (pinfunction "P$1_P$1") (pintype "bidirectional"))
    )
  )
)
